# Crutch_light_Switch.net
KiCad netlist of a schematic drawn in EAGLE
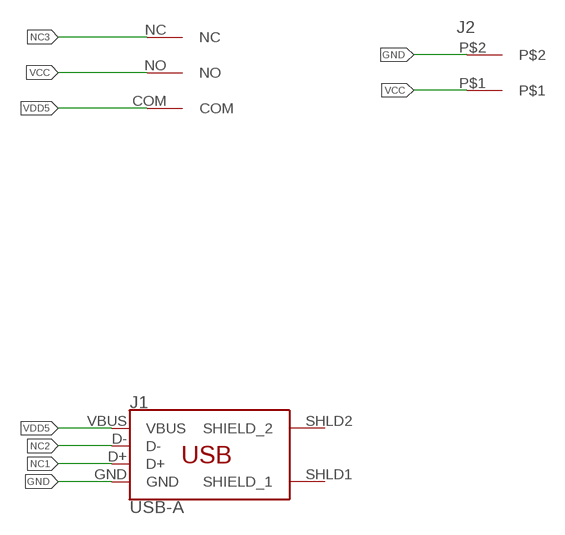
[diagram p0: schematic, sheet 1]

(export (version "E")
  (design (tool "Eeschema 10.0.6"))
  (components
    (comp (ref "J1")
      (value "USB-A")
      (footprint "eagle-import:USB_A_SMT")
      (fields (field (name "PARTNO") "87583-3010RPALF"))
      (libsource (lib "eagle-import") (part "USB_A"))
    )
    (comp (ref "J2")
      (value "2-pos")
      (footprint "eagle-import:2_3.81MM_PITCH")
      (fields (field (name "PARTNO") "691322310002"))
      (libsource (lib "eagle-import") (part "3.81MM_1_X_2_RT_ANGLE_PLUG_HEADER"))
    )
    (comp (ref "U$1")
      (value "LIMIT_SWITCH_D2HW-BR201DR")
      (footprint "eagle-import:LIMIT_SWITCH_D2HW-BR201DR")
      (libsource (lib "eagle-import") (part "LIMIT_SWITCH_D2HW-BR201DR"))
    )
  )
  (nets
    (net (code "1") (name "GND") (class "Default")
      (node (ref "J1") (pin "GND") (pinfunction "GND_GND") (pintype "power_in"))
      (node (ref "J2") (pin "P$2") (pinfunction "P$2_P$2") (pintype "bidirectional"))
    )
    (net (code "2") (name "NC1") (class "Default")
      (node (ref "J1") (pin "D+") (pinfunction "D+_D+") (pintype "bidirectional"))
    )
    (net (code "3") (name "NC2") (class "Default")
      (node (ref "J1") (pin "D-") (pinfunction "D-_D-") (pintype "bidirectional"))
    )
    (net (code "4") (name "NC3") (class "Default")
      (node (ref "U$1") (pin "NC") (pinfunction "NC_NC") (pintype "bidirectional"))
    )
    (net (code "5") (name "VCC") (class "Default")
      (node (ref "J2") (pin "P$1") (pinfunction "P$1_P$1") (pintype "bidirectional"))
      (node (ref "U$1") (pin "NO") (pinfunction "NO_NO") (pintype "bidirectional"))
    )
    (net (code "6") (name "VDD5") (class "Default")
      (node (ref "J1") (pin "VBUS") (pinfunction "VBUS_VBUS") (pintype "power_in"))
      (node (ref "U$1") (pin "COM") (pinfunction "COM_COM") (pintype "bidirectional"))
    )
    (net (code "7") (name "unconnected-(J1-SHIELD_1-PadSHLD1)") (class "Default")
      (node (ref "J1") (pin "SHLD1") (pinfunction "SHIELD_1_SHLD1") (pintype "bidirectional"))
    )
    (net (code "8") (name "unconnected-(J1-SHIELD_2-PadSHLD2)") (class "Default")
      (node (ref "J1") (pin "SHLD2") (pinfunction "SHIELD_2_SHLD2") (pintype "bidirectional"))
    )
  )
)
